# MHI-SPI_v1_0.net
KiCad netlist of a schematic drawn in EAGLE
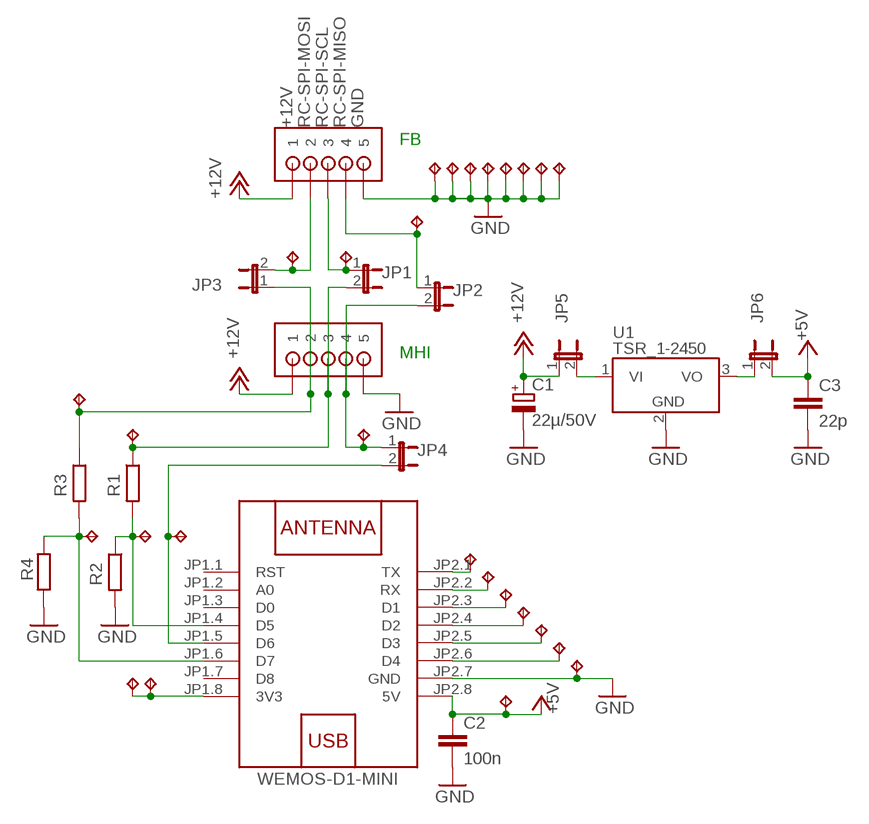
[diagram p0: schematic, sheet 1]

(export (version "E")
  (design (tool "Eeschema 10.0.6"))
  (components
    (comp (ref "C1")
      (value "22µ/50V")
      (footprint "eagle-import:E5-10,5")
      (libsource (lib "eagle-import") (part "CPOL-EUE5-10.5"))
    )
    (comp (ref "C2")
      (value "100n")
      (footprint "eagle-import:C025-024X044")
      (libsource (lib "eagle-import") (part "C-EU025-024X044"))
    )
    (comp (ref "C3")
      (value "22p")
      (footprint "eagle-import:C025-024X044")
      (libsource (lib "eagle-import") (part "C-EU025-024X044"))
    )
    (comp (ref "JP1")
      (value "JP1E")
      (footprint "eagle-import:JP1")
      (libsource (lib "eagle-import") (part "JP1E"))
    )
    (comp (ref "JP2")
      (value "JP1E")
      (footprint "eagle-import:JP1")
      (libsource (lib "eagle-import") (part "JP1E"))
    )
    (comp (ref "JP3")
      (value "JP1E")
      (footprint "eagle-import:JP1")
      (libsource (lib "eagle-import") (part "JP1E"))
    )
    (comp (ref "JP4")
      (value "JP1E")
      (footprint "eagle-import:JP1")
      (libsource (lib "eagle-import") (part "JP1E"))
    )
    (comp (ref "JP5")
      (value "JP1E")
      (footprint "eagle-import:JP1")
      (libsource (lib "eagle-import") (part "JP1E"))
    )
    (comp (ref "JP6")
      (value "JP1E")
      (footprint "eagle-import:JP1")
      (libsource (lib "eagle-import") (part "JP1E"))
    )
    (comp (ref "R1")
      (value "R-EU_VMTA55")
      (footprint "eagle-import:VMTA55")
      (libsource (lib "eagle-import") (part "R-EU_VMTA55"))
    )
    (comp (ref "R2")
      (value "R-EU_VMTA55")
      (footprint "eagle-import:VMTA55")
      (libsource (lib "eagle-import") (part "R-EU_VMTA55"))
    )
    (comp (ref "R3")
      (value "R-EU_VMTA55")
      (footprint "eagle-import:VMTA55")
      (libsource (lib "eagle-import") (part "R-EU_VMTA55"))
    )
    (comp (ref "R4")
      (value "R-EU_VMTA55")
      (footprint "eagle-import:VMTA55")
      (libsource (lib "eagle-import") (part "R-EU_VMTA55"))
    )
    (comp (ref "TP1")
      (value "TPPAD1-13")
      (footprint "eagle-import:P1-13")
      (libsource (lib "eagle-import") (part "TPPAD1-13"))
    )
    (comp (ref "TP2")
      (value "TPPAD1-13")
      (footprint "eagle-import:P1-13")
      (libsource (lib "eagle-import") (part "TPPAD1-13"))
    )
    (comp (ref "TP3")
      (value "TPPAD1-13")
      (footprint "eagle-import:P1-13")
      (libsource (lib "eagle-import") (part "TPPAD1-13"))
    )
    (comp (ref "TP4")
      (value "TPPAD1-13")
      (footprint "eagle-import:P1-13")
      (libsource (lib "eagle-import") (part "TPPAD1-13"))
    )
    (comp (ref "TP5")
      (value "TPPAD1-13")
      (footprint "eagle-import:P1-13")
      (libsource (lib "eagle-import") (part "TPPAD1-13"))
    )
    (comp (ref "TP6")
      (value "TPPAD1-13")
      (footprint "eagle-import:P1-13")
      (libsource (lib "eagle-import") (part "TPPAD1-13"))
    )
    (comp (ref "TP7")
      (value "TPPAD1-13")
      (footprint "eagle-import:P1-13")
      (libsource (lib "eagle-import") (part "TPPAD1-13"))
    )
    (comp (ref "TP8")
      (value "TPPAD1-13")
      (footprint "eagle-import:P1-13")
      (libsource (lib "eagle-import") (part "TPPAD1-13"))
    )
    (comp (ref "TP9")
      (value "TPPAD1-13")
      (footprint "eagle-import:P1-13")
      (libsource (lib "eagle-import") (part "TPPAD1-13"))
    )
    (comp (ref "TP10")
      (value "TPPAD1-13")
      (footprint "eagle-import:P1-13")
      (libsource (lib "eagle-import") (part "TPPAD1-13"))
    )
    (comp (ref "TP11")
      (value "TPPAD1-13")
      (footprint "eagle-import:P1-13")
      (libsource (lib "eagle-import") (part "TPPAD1-13"))
    )
    (comp (ref "TP12")
      (value "TPPAD1-13")
      (footprint "eagle-import:P1-13")
      (libsource (lib "eagle-import") (part "TPPAD1-13"))
    )
    (comp (ref "TP13")
      (value "TPPAD1-13")
      (footprint "eagle-import:P1-13")
      (libsource (lib "eagle-import") (part "TPPAD1-13"))
    )
    (comp (ref "TP14")
      (value "TPPAD1-13")
      (footprint "eagle-import:P1-13")
      (libsource (lib "eagle-import") (part "TPPAD1-13"))
    )
    (comp (ref "TP15")
      (value "TPPAD1-13")
      (footprint "eagle-import:P1-13")
      (libsource (lib "eagle-import") (part "TPPAD1-13"))
    )
    (comp (ref "TP16")
      (value "TPPAD1-13")
      (footprint "eagle-import:P1-13")
      (libsource (lib "eagle-import") (part "TPPAD1-13"))
    )
    (comp (ref "TP17")
      (value "TPPAD1-13")
      (footprint "eagle-import:P1-13")
      (libsource (lib "eagle-import") (part "TPPAD1-13"))
    )
    (comp (ref "TP18")
      (value "TPPAD1-13")
      (footprint "eagle-import:P1-13")
      (libsource (lib "eagle-import") (part "TPPAD1-13"))
    )
    (comp (ref "TP19")
      (value "TPPAD1-13")
      (footprint "eagle-import:P1-13")
      (libsource (lib "eagle-import") (part "TPPAD1-13"))
    )
    (comp (ref "TP20")
      (value "TPPAD1-13")
      (footprint "eagle-import:P1-13")
      (libsource (lib "eagle-import") (part "TPPAD1-13"))
    )
    (comp (ref "TP21")
      (value "TPPAD1-13")
      (footprint "eagle-import:P1-13")
      (libsource (lib "eagle-import") (part "TPPAD1-13"))
    )
    (comp (ref "TP22")
      (value "TPPAD1-13")
      (footprint "eagle-import:P1-13")
      (libsource (lib "eagle-import") (part "TPPAD1-13"))
    )
    (comp (ref "TP23")
      (value "TPPAD1-13")
      (footprint "eagle-import:P1-13")
      (libsource (lib "eagle-import") (part "TPPAD1-13"))
    )
    (comp (ref "TP24")
      (value "TPPAD1-13")
      (footprint "eagle-import:P1-13")
      (libsource (lib "eagle-import") (part "TPPAD1-13"))
    )
    (comp (ref "TP25")
      (value "TPPAD1-13")
      (footprint "eagle-import:P1-13")
      (libsource (lib "eagle-import") (part "TPPAD1-13"))
    )
    (comp (ref "TP26")
      (value "TPPAD1-13")
      (footprint "eagle-import:P1-13")
      (libsource (lib "eagle-import") (part "TPPAD1-13"))
    )
    (comp (ref "TP27")
      (value "TPPAD1-13")
      (footprint "eagle-import:P1-13")
      (libsource (lib "eagle-import") (part "TPPAD1-13"))
    )
    (comp (ref "U$1")
      (value "WEMOS-D1-MINI")
      (footprint "eagle-import:WEMOS-D1-MINI")
      (libsource (lib "eagle-import") (part "WEMOS-D1-MINI"))
    )
    (comp (ref "U$4")
      (value "JST-PH_5-PIN_HEADER")
      (footprint "eagle-import:JST_B5B-PH_HEADER")
      (libsource (lib "eagle-import") (part "JST-PH_5-PIN_HEADER"))
    )
    (comp (ref "U$5")
      (value "JST-PH_5-PIN_HEADER")
      (footprint "eagle-import:JST_B5B-PH_HEADER")
      (libsource (lib "eagle-import") (part "JST-PH_5-PIN_HEADER"))
    )
    (comp (ref "U1")
      (value "TSR_1-2450")
      (footprint "eagle-import:TSR-1")
      (libsource (lib "eagle-import") (part "TSR_1-24_"))
    )
  )
  (nets
    (net (code "1") (name "+5V") (class "Default")
      (node (ref "C2") (pin "1") (pinfunction "1_1") (pintype "passive"))
      (node (ref "C3") (pin "1") (pinfunction "1_1") (pintype "passive"))
      (node (ref "JP6") (pin "2") (pinfunction "2_2") (pintype "passive"))
      (node (ref "TP21") (pin "TP") (pinfunction "TP_TP") (pintype "input"))
      (node (ref "U$1") (pin "JP2.8") (pinfunction "5V_JP2.8") (pintype "power_in"))
    )
    (net (code "2") (name "+12V") (class "Default")
      (node (ref "C1") (pin "+") (pinfunction "+_+") (pintype "passive"))
      (node (ref "JP5") (pin "1") (pinfunction "1_1") (pintype "passive"))
      (node (ref "U$4") (pin "P1") (pinfunction "1_P1") (pintype "bidirectional"))
      (node (ref "U$5") (pin "P1") (pinfunction "1_P1") (pintype "bidirectional"))
    )
    (net (code "3") (name "/RC-SPI-MISO") (class "Default")
      (node (ref "JP2") (pin "1") (pinfunction "1_1") (pintype "passive"))
      (node (ref "TP5") (pin "TP") (pinfunction "TP_TP") (pintype "input"))
      (node (ref "U$4") (pin "P4") (pinfunction "4_P4") (pintype "bidirectional"))
    )
    (net (code "4") (name "/RC-SPI-MOSI") (class "Default")
      (node (ref "JP3") (pin "2") (pinfunction "2_2") (pintype "passive"))
      (node (ref "TP7") (pin "TP") (pinfunction "TP_TP") (pintype "input"))
      (node (ref "U$4") (pin "P2") (pinfunction "2_P2") (pintype "bidirectional"))
    )
    (net (code "5") (name "/RC-SPI-SCL") (class "Default")
      (node (ref "JP1") (pin "1") (pinfunction "1_1") (pintype "passive"))
      (node (ref "TP6") (pin "TP") (pinfunction "TP_TP") (pintype "input"))
      (node (ref "U$4") (pin "P3") (pinfunction "3_P3") (pintype "bidirectional"))
    )
    (net (code "6") (name "GND") (class "Default")
      (node (ref "C1") (pin "-") (pinfunction "-_-") (pintype "passive"))
      (node (ref "C2") (pin "2") (pinfunction "2_2") (pintype "passive"))
      (node (ref "C3") (pin "2") (pinfunction "2_2") (pintype "passive"))
      (node (ref "R2") (pin "2") (pinfunction "2_2") (pintype "passive"))
      (node (ref "R4") (pin "1") (pinfunction "1_1") (pintype "passive"))
      (node (ref "TP1") (pin "TP") (pinfunction "TP_TP") (pintype "input"))
      (node (ref "TP2") (pin "TP") (pinfunction "TP_TP") (pintype "input"))
      (node (ref "TP20") (pin "TP") (pinfunction "TP_TP") (pintype "input"))
      (node (ref "TP24") (pin "TP") (pinfunction "TP_TP") (pintype "input"))
      (node (ref "TP25") (pin "TP") (pinfunction "TP_TP") (pintype "input"))
      (node (ref "TP26") (pin "TP") (pinfunction "TP_TP") (pintype "input"))
      (node (ref "TP27") (pin "TP") (pinfunction "TP_TP") (pintype "input"))
      (node (ref "TP3") (pin "TP") (pinfunction "TP_TP") (pintype "input"))
      (node (ref "TP4") (pin "TP") (pinfunction "TP_TP") (pintype "input"))
      (node (ref "U$1") (pin "JP2.7") (pinfunction "GND_JP2.7") (pintype "power_in"))
      (node (ref "U$4") (pin "P5") (pinfunction "5_P5") (pintype "bidirectional"))
      (node (ref "U$5") (pin "P5") (pinfunction "5_P5") (pintype "bidirectional"))
      (node (ref "U1") (pin "2") (pinfunction "GND_2") (pintype "power_in"))
    )
    (net (code "7") (name "Net-(U$1-3V3)") (class "Default")
      (node (ref "TP22") (pin "TP") (pinfunction "TP_TP") (pintype "input"))
      (node (ref "TP23") (pin "TP") (pinfunction "TP_TP") (pintype "input"))
      (node (ref "U$1") (pin "JP1.8") (pinfunction "3V3_JP1.8") (pintype "power_in"))
    )
    (net (code "8") (name "Net-(U$1-D1)") (class "Default")
      (node (ref "TP16") (pin "TP") (pinfunction "TP_TP") (pintype "input"))
      (node (ref "U$1") (pin "JP2.3") (pinfunction "D1_JP2.3") (pintype "bidirectional"))
    )
    (net (code "9") (name "Net-(U$1-D2)") (class "Default")
      (node (ref "TP17") (pin "TP") (pinfunction "TP_TP") (pintype "input"))
      (node (ref "U$1") (pin "JP2.4") (pinfunction "D2_JP2.4") (pintype "bidirectional"))
    )
    (net (code "10") (name "Net-(U$1-D3)") (class "Default")
      (node (ref "TP18") (pin "TP") (pinfunction "TP_TP") (pintype "input"))
      (node (ref "U$1") (pin "JP2.5") (pinfunction "D3_JP2.5") (pintype "bidirectional"))
    )
    (net (code "11") (name "Net-(U$1-D4)") (class "Default")
      (node (ref "TP19") (pin "TP") (pinfunction "TP_TP") (pintype "input"))
      (node (ref "U$1") (pin "JP2.6") (pinfunction "D4_JP2.6") (pintype "bidirectional"))
    )
    (net (code "12") (name "Net-(U$1-D5)") (class "Default")
      (node (ref "R1") (pin "2") (pinfunction "2_2") (pintype "passive"))
      (node (ref "R2") (pin "1") (pinfunction "1_1") (pintype "passive"))
      (node (ref "TP12") (pin "TP") (pinfunction "TP_TP") (pintype "input"))
      (node (ref "U$1") (pin "JP1.4") (pinfunction "D5_JP1.4") (pintype "bidirectional"))
    )
    (net (code "13") (name "Net-(U$1-D6)") (class "Default")
      (node (ref "JP4") (pin "2") (pinfunction "2_2") (pintype "passive"))
      (node (ref "TP11") (pin "TP") (pinfunction "TP_TP") (pintype "input"))
      (node (ref "U$1") (pin "JP1.5") (pinfunction "D6_JP1.5") (pintype "bidirectional"))
    )
    (net (code "14") (name "Net-(U$1-D7)") (class "Default")
      (node (ref "R3") (pin "2") (pinfunction "2_2") (pintype "passive"))
      (node (ref "R4") (pin "2") (pinfunction "2_2") (pintype "passive"))
      (node (ref "TP13") (pin "TP") (pinfunction "TP_TP") (pintype "input"))
      (node (ref "U$1") (pin "JP1.6") (pinfunction "D7_JP1.6") (pintype "bidirectional"))
    )
    (net (code "15") (name "Net-(U$1-RX)") (class "Default")
      (node (ref "TP15") (pin "TP") (pinfunction "TP_TP") (pintype "input"))
      (node (ref "U$1") (pin "JP2.2") (pinfunction "RX_JP2.2") (pintype "bidirectional"))
    )
    (net (code "16") (name "Net-(U$1-TX)") (class "Default")
      (node (ref "TP14") (pin "TP") (pinfunction "TP_TP") (pintype "input"))
      (node (ref "U$1") (pin "JP2.1") (pinfunction "TX_JP2.1") (pintype "bidirectional"))
    )
    (net (code "17") (name "Net-(U$5-2)") (class "Default")
      (node (ref "JP3") (pin "1") (pinfunction "1_1") (pintype "passive"))
      (node (ref "R3") (pin "1") (pinfunction "1_1") (pintype "passive"))
      (node (ref "TP10") (pin "TP") (pinfunction "TP_TP") (pintype "input"))
      (node (ref "U$5") (pin "P2") (pinfunction "2_P2") (pintype "bidirectional"))
    )
    (net (code "18") (name "Net-(U$5-3)") (class "Default")
      (node (ref "JP1") (pin "2") (pinfunction "2_2") (pintype "passive"))
      (node (ref "R1") (pin "1") (pinfunction "1_1") (pintype "passive"))
      (node (ref "TP9") (pin "TP") (pinfunction "TP_TP") (pintype "input"))
      (node (ref "U$5") (pin "P3") (pinfunction "3_P3") (pintype "bidirectional"))
    )
    (net (code "19") (name "Net-(U$5-4)") (class "Default")
      (node (ref "JP2") (pin "2") (pinfunction "2_2") (pintype "passive"))
      (node (ref "JP4") (pin "1") (pinfunction "1_1") (pintype "passive"))
      (node (ref "TP8") (pin "TP") (pinfunction "TP_TP") (pintype "input"))
      (node (ref "U$5") (pin "P4") (pinfunction "4_P4") (pintype "bidirectional"))
    )
    (net (code "20") (name "Net-(U1-VI)") (class "Default")
      (node (ref "JP5") (pin "2") (pinfunction "2_2") (pintype "passive"))
      (node (ref "U1") (pin "1") (pinfunction "VI_1") (pintype "power_in"))
    )
    (net (code "21") (name "Net-(U1-VO)") (class "Default")
      (node (ref "JP6") (pin "1") (pinfunction "1_1") (pintype "passive"))
      (node (ref "U1") (pin "3") (pinfunction "VO_3") (pintype "power_in"))
    )
    (net (code "22") (name "unconnected-(U$1-A0-PadJP1.2)") (class "Default")
      (node (ref "U$1") (pin "JP1.2") (pinfunction "A0_JP1.2") (pintype "bidirectional"))
    )
    (net (code "23") (name "unconnected-(U$1-D0-PadJP1.3)") (class "Default")
      (node (ref "U$1") (pin "JP1.3") (pinfunction "D0_JP1.3") (pintype "bidirectional"))
    )
    (net (code "24") (name "unconnected-(U$1-D8-PadJP1.7)") (class "Default")
      (node (ref "U$1") (pin "JP1.7") (pinfunction "D8_JP1.7") (pintype "bidirectional"))
    )
    (net (code "25") (name "unconnected-(U$1-RST-PadJP1.1)") (class "Default")
      (node (ref "U$1") (pin "JP1.1") (pinfunction "RST_JP1.1") (pintype "bidirectional"))
    )
  )
)
